# ATtiny-13-adapter.net
KiCad netlist of a schematic drawn in EAGLE
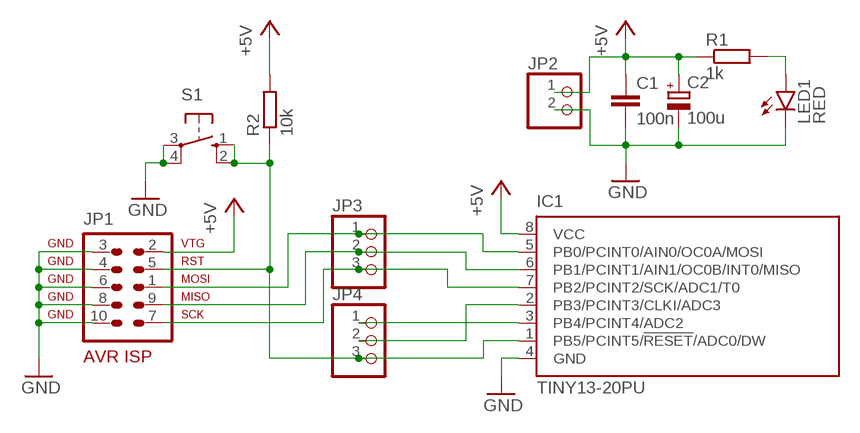
[diagram p0: schematic, sheet 1]

(export (version "E")
  (design (tool "Eeschema 10.0.6"))
  (components
    (comp (ref "C1")
      (value "100n")
      (footprint "eagle-import:C1206")
      (libsource (lib "eagle-import") (part "C-EUC1206"))
    )
    (comp (ref "C2")
      (value "100u")
      (footprint "eagle-import:E2-5")
      (libsource (lib "eagle-import") (part "CPOL-EUE2-5"))
    )
    (comp (ref "IC1")
      (value "TINY13-20PU")
      (footprint "eagle-import:DIL08")
      (fields (field (name "MPN") "ATTINY13-20PU"))
      (libsource (lib "eagle-import") (part "TINY13PU-20"))
    )
    (comp (ref "JP1")
      (value "AVR-ISP-10ML")
      (footprint "eagle-import:ML10")
      (libsource (lib "eagle-import") (part "AVR-ISP-10ML"))
    )
    (comp (ref "JP2")
      (value "PINHD-1X2")
      (footprint "eagle-import:1X02")
      (libsource (lib "eagle-import") (part "PINHD-1X2"))
    )
    (comp (ref "JP3")
      (value "PINHD-1X3")
      (footprint "eagle-import:1X03")
      (libsource (lib "eagle-import") (part "PINHD-1X3"))
    )
    (comp (ref "JP4")
      (value "PINHD-1X3")
      (footprint "eagle-import:1X03")
      (libsource (lib "eagle-import") (part "PINHD-1X3"))
    )
    (comp (ref "LED1")
      (value "RED")
      (footprint "eagle-import:LED3MM")
      (libsource (lib "eagle-import") (part "LED3MM"))
    )
    (comp (ref "R1")
      (value "1k")
      (footprint "eagle-import:R1206")
      (libsource (lib "eagle-import") (part "R-EU_R1206"))
    )
    (comp (ref "R2")
      (value "10k")
      (footprint "eagle-import:R1206")
      (libsource (lib "eagle-import") (part "R-EU_R1206"))
    )
    (comp (ref "S1")
      (value "10-XX")
      (footprint "eagle-import:B3F-10XX")
      (fields (field (name "MPN") "B3F-1000"))
      (libsource (lib "eagle-import") (part "10-XX"))
    )
  )
  (nets
    (net (code "1") (name "+5V") (class "Default")
      (node (ref "C1") (pin "1") (pinfunction "1_1") (pintype "passive"))
      (node (ref "C2") (pin "+") (pinfunction "+_+") (pintype "passive"))
      (node (ref "IC1") (pin "8") (pinfunction "VCC_8") (pintype "power_in"))
      (node (ref "JP1") (pin "2") (pinfunction "2_2") (pintype "passive"))
      (node (ref "JP2") (pin "1") (pinfunction "1_1") (pintype "passive"))
      (node (ref "R1") (pin "1") (pinfunction "1_1") (pintype "passive"))
      (node (ref "R2") (pin "2") (pinfunction "2_2") (pintype "passive"))
    )
    (net (code "2") (name "GND") (class "Default")
      (node (ref "C1") (pin "2") (pinfunction "2_2") (pintype "passive"))
      (node (ref "C2") (pin "-") (pinfunction "-_-") (pintype "passive"))
      (node (ref "IC1") (pin "4") (pinfunction "GND_4") (pintype "power_in"))
      (node (ref "JP1") (pin "10") (pinfunction "10_10") (pintype "passive"))
      (node (ref "JP1") (pin "3") (pinfunction "3_3") (pintype "passive"))
      (node (ref "JP1") (pin "4") (pinfunction "4_4") (pintype "passive"))
      (node (ref "JP1") (pin "6") (pinfunction "6_6") (pintype "passive"))
      (node (ref "JP1") (pin "8") (pinfunction "8_8") (pintype "passive"))
      (node (ref "JP2") (pin "2") (pinfunction "2_2") (pintype "passive"))
      (node (ref "LED1") (pin "K") (pinfunction "C_K") (pintype "passive"))
      (node (ref "S1") (pin "3") (pinfunction "P_3") (pintype "passive"))
      (node (ref "S1") (pin "4") (pinfunction "P1_4") (pintype "passive"))
    )
    (net (code "3") (name "Net-(IC1-PB0{slash}PCINT0{slash}AIN0{slash}OC0A{slash}MOSI)") (class "Default")
      (node (ref "IC1") (pin "5") (pinfunction "PB0/PCINT0/AIN0/OC0A/MOSI_5") (pintype "bidirectional"))
      (node (ref "JP1") (pin "1") (pinfunction "1_1") (pintype "passive"))
      (node (ref "JP3") (pin "1") (pinfunction "1_1") (pintype "passive"))
    )
    (net (code "4") (name "Net-(IC1-PB1{slash}PCINT1{slash}AIN1{slash}OC0B{slash}INT0{slash}MISO)") (class "Default")
      (node (ref "IC1") (pin "6") (pinfunction "PB1/PCINT1/AIN1/OC0B/INT0/MISO_6") (pintype "bidirectional"))
      (node (ref "JP1") (pin "9") (pinfunction "9_9") (pintype "passive"))
      (node (ref "JP3") (pin "2") (pinfunction "2_2") (pintype "passive"))
    )
    (net (code "5") (name "Net-(IC1-PB2{slash}PCINT2{slash}SCK{slash}ADC1{slash}T0)") (class "Default")
      (node (ref "IC1") (pin "7") (pinfunction "PB2/PCINT2/SCK/ADC1/T0_7") (pintype "bidirectional"))
      (node (ref "JP1") (pin "7") (pinfunction "7_7") (pintype "passive"))
      (node (ref "JP3") (pin "3") (pinfunction "3_3") (pintype "passive"))
    )
    (net (code "6") (name "Net-(IC1-PB3{slash}PCINT3{slash}CLKI{slash}ADC3)") (class "Default")
      (node (ref "IC1") (pin "2") (pinfunction "PB3/PCINT3/CLKI/ADC3_2") (pintype "bidirectional"))
      (node (ref "JP4") (pin "2") (pinfunction "2_2") (pintype "passive"))
    )
    (net (code "7") (name "Net-(IC1-PB4{slash}PCINT4{slash}ADC2)") (class "Default")
      (node (ref "IC1") (pin "3") (pinfunction "PB4/PCINT4/ADC2_3") (pintype "bidirectional"))
      (node (ref "JP4") (pin "1") (pinfunction "1_1") (pintype "passive"))
    )
    (net (code "8") (name "Net-(IC1-PB5{slash}PCINT5{slash}~{RESET}{slash}ADC0{slash}DW)") (class "Default")
      (node (ref "IC1") (pin "1") (pinfunction "PB5/PCINT5/~{RESET}/ADC0/DW_1") (pintype "bidirectional"))
      (node (ref "JP1") (pin "5") (pinfunction "5_5") (pintype "passive"))
      (node (ref "JP4") (pin "3") (pinfunction "3_3") (pintype "passive"))
      (node (ref "R2") (pin "1") (pinfunction "1_1") (pintype "passive"))
      (node (ref "S1") (pin "1") (pinfunction "S_1") (pintype "passive"))
      (node (ref "S1") (pin "2") (pinfunction "S1_2") (pintype "passive"))
    )
    (net (code "9") (name "Net-(LED1-PadA)") (class "Default")
      (node (ref "LED1") (pin "A") (pinfunction "A_A") (pintype "passive"))
      (node (ref "R1") (pin "2") (pinfunction "2_2") (pintype "passive"))
    )
  )
)
